# Soic8ToDip8.net
KiCad netlist of a schematic drawn in EAGLE
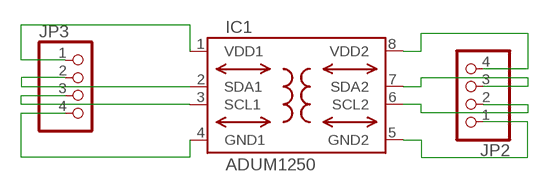
[diagram p0: schematic, sheet 1]

(export (version "E")
  (design (tool "Eeschema 10.0.6"))
  (components
    (comp (ref "IC1")
      (value "ADUM1250")
      (footprint "eagle-import:SO8-COOL")
      (libsource (lib "eagle-import") (part "ADUM1250"))
    )
    (comp (ref "JP2")
      (value "PINHD-1X4")
      (footprint "eagle-import:1X04")
      (libsource (lib "eagle-import") (part "PINHD-1X4"))
    )
    (comp (ref "JP3")
      (value "PINHD-1X4")
      (footprint "eagle-import:1X04")
      (libsource (lib "eagle-import") (part "PINHD-1X4"))
    )
  )
  (nets
    (net (code "1") (name "Net-(IC1-GND1)") (class "Default")
      (node (ref "IC1") (pin "4") (pinfunction "GND1_4") (pintype "power_in"))
      (node (ref "JP3") (pin "4") (pinfunction "4_4") (pintype "passive"))
    )
    (net (code "2") (name "Net-(IC1-GND2)") (class "Default")
      (node (ref "IC1") (pin "5") (pinfunction "GND2_5") (pintype "power_in"))
      (node (ref "JP2") (pin "1") (pinfunction "1_1") (pintype "passive"))
    )
    (net (code "3") (name "Net-(IC1-SCL1)") (class "Default")
      (node (ref "IC1") (pin "3") (pinfunction "SCL1_3") (pintype "bidirectional"))
      (node (ref "JP3") (pin "3") (pinfunction "3_3") (pintype "passive"))
    )
    (net (code "4") (name "Net-(IC1-SCL2)") (class "Default")
      (node (ref "IC1") (pin "6") (pinfunction "SCL2_6") (pintype "bidirectional"))
      (node (ref "JP2") (pin "2") (pinfunction "2_2") (pintype "passive"))
    )
    (net (code "5") (name "Net-(IC1-SDA1)") (class "Default")
      (node (ref "IC1") (pin "2") (pinfunction "SDA1_2") (pintype "bidirectional"))
      (node (ref "JP3") (pin "2") (pinfunction "2_2") (pintype "passive"))
    )
    (net (code "6") (name "Net-(IC1-SDA2)") (class "Default")
      (node (ref "IC1") (pin "7") (pinfunction "SDA2_7") (pintype "bidirectional"))
      (node (ref "JP2") (pin "3") (pinfunction "3_3") (pintype "passive"))
    )
    (net (code "7") (name "Net-(IC1-VDD1)") (class "Default")
      (node (ref "IC1") (pin "1") (pinfunction "VDD1_1") (pintype "power_in"))
      (node (ref "JP3") (pin "1") (pinfunction "1_1") (pintype "passive"))
    )
    (net (code "8") (name "Net-(IC1-VDD2)") (class "Default")
      (node (ref "IC1") (pin "8") (pinfunction "VDD2_8") (pintype "power_in"))
      (node (ref "JP2") (pin "4") (pinfunction "4_4") (pintype "passive"))
    )
  )
)
